# Left_Ear_Board.net
KiCad netlist of a schematic drawn in EAGLE
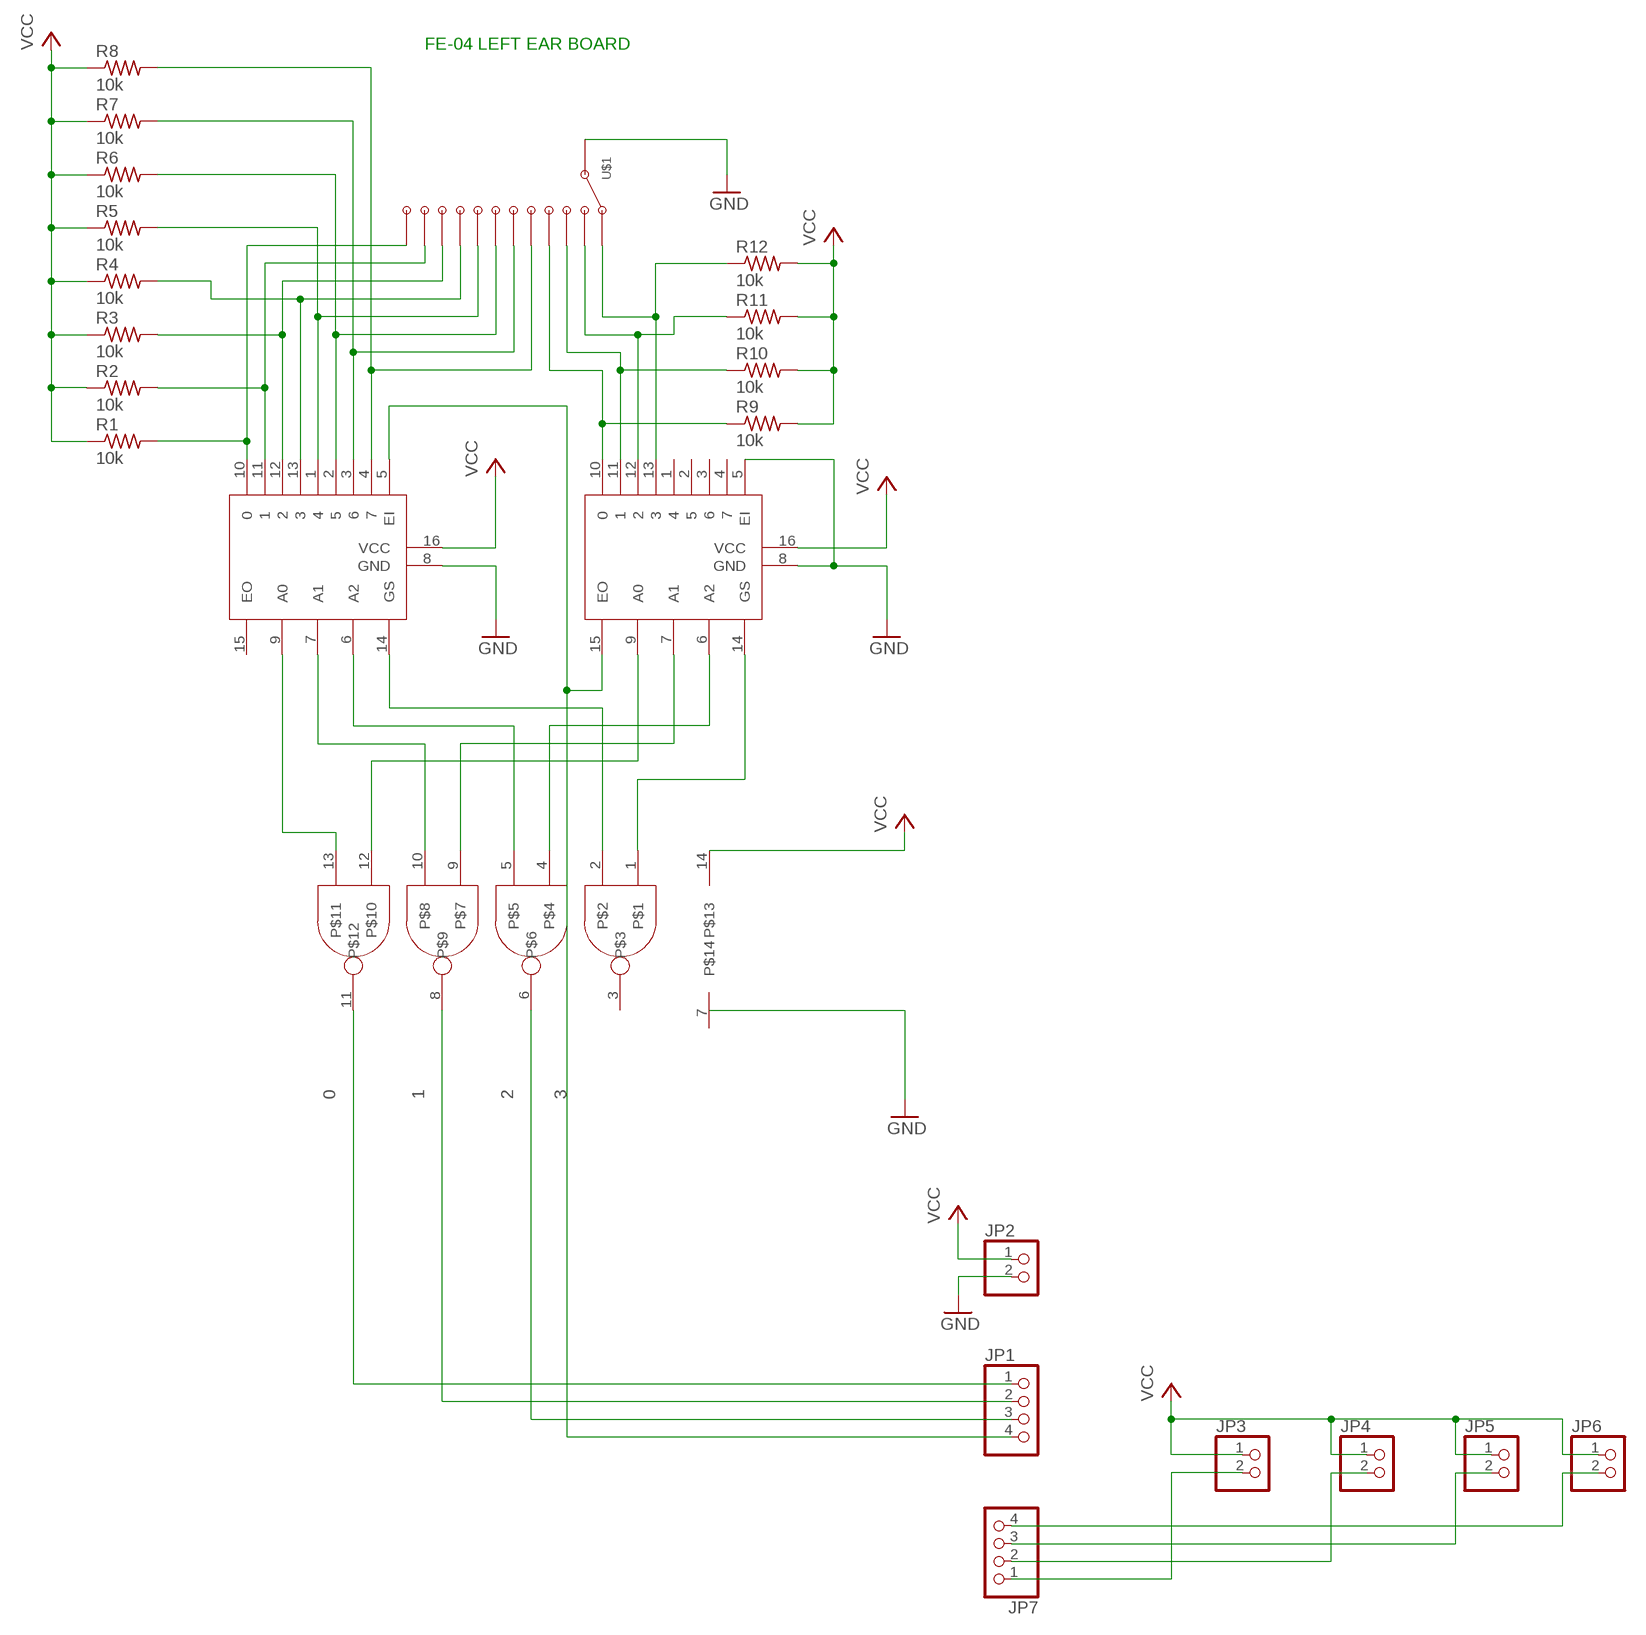
[diagram p0: schematic, sheet 1]

(export (version "E")
  (design (tool "Eeschema 10.0.6"))
  (components
    (comp (ref "JP1")
      (value "PINHD-1X4")
      (footprint "eagle-import:1X04")
      (libsource (lib "eagle-import") (part "PINHD-1X4"))
    )
    (comp (ref "JP2")
      (value "PINHD-1X2")
      (footprint "eagle-import:1X02")
      (libsource (lib "eagle-import") (part "PINHD-1X2"))
    )
    (comp (ref "JP3")
      (value "PINHD-1X2")
      (footprint "eagle-import:1X02")
      (libsource (lib "eagle-import") (part "PINHD-1X2"))
    )
    (comp (ref "JP4")
      (value "PINHD-1X2")
      (footprint "eagle-import:1X02")
      (libsource (lib "eagle-import") (part "PINHD-1X2"))
    )
    (comp (ref "JP5")
      (value "PINHD-1X2")
      (footprint "eagle-import:1X02")
      (libsource (lib "eagle-import") (part "PINHD-1X2"))
    )
    (comp (ref "JP6")
      (value "PINHD-1X2")
      (footprint "eagle-import:1X02")
      (libsource (lib "eagle-import") (part "PINHD-1X2"))
    )
    (comp (ref "JP7")
      (value "PINHD-1X4")
      (footprint "eagle-import:1X04")
      (libsource (lib "eagle-import") (part "PINHD-1X4"))
    )
    (comp (ref "R1")
      (value "10k")
      (footprint "eagle-import:R0603")
      (fields (field (name "PARTNO") "ERJ-3EKF2201V"))
      (libsource (lib "eagle-import") (part "R-US_R0603"))
    )
    (comp (ref "R2")
      (value "10k")
      (footprint "eagle-import:R0603")
      (fields (field (name "PARTNO") "ERJ-3EKF2201V"))
      (libsource (lib "eagle-import") (part "R-US_R0603"))
    )
    (comp (ref "R3")
      (value "10k")
      (footprint "eagle-import:R0603")
      (fields (field (name "PARTNO") "ERJ-3EKF2201V"))
      (libsource (lib "eagle-import") (part "R-US_R0603"))
    )
    (comp (ref "R4")
      (value "10k")
      (footprint "eagle-import:R0603")
      (fields (field (name "PARTNO") "ERJ-3EKF2201V"))
      (libsource (lib "eagle-import") (part "R-US_R0603"))
    )
    (comp (ref "R5")
      (value "10k")
      (footprint "eagle-import:R0603")
      (fields (field (name "PARTNO") "ERJ-3EKF2201V"))
      (libsource (lib "eagle-import") (part "R-US_R0603"))
    )
    (comp (ref "R6")
      (value "10k")
      (footprint "eagle-import:R0603")
      (fields (field (name "PARTNO") "ERJ-3EKF2201V"))
      (libsource (lib "eagle-import") (part "R-US_R0603"))
    )
    (comp (ref "R7")
      (value "10k")
      (footprint "eagle-import:R0603")
      (fields (field (name "PARTNO") "ERJ-3EKF2201V"))
      (libsource (lib "eagle-import") (part "R-US_R0603"))
    )
    (comp (ref "R8")
      (value "10k")
      (footprint "eagle-import:R0603")
      (fields (field (name "PARTNO") "ERJ-3EKF2201V"))
      (libsource (lib "eagle-import") (part "R-US_R0603"))
    )
    (comp (ref "R9")
      (value "10k")
      (footprint "eagle-import:R0603")
      (fields (field (name "PARTNO") "ERJ-3EKF2201V"))
      (libsource (lib "eagle-import") (part "R-US_R0603"))
    )
    (comp (ref "R10")
      (value "10k")
      (footprint "eagle-import:R0603")
      (fields (field (name "PARTNO") "ERJ-3EKF2201V"))
      (libsource (lib "eagle-import") (part "R-US_R0603"))
    )
    (comp (ref "R11")
      (value "10k")
      (footprint "eagle-import:R0603")
      (fields (field (name "PARTNO") "ERJ-3EKF2201V"))
      (libsource (lib "eagle-import") (part "R-US_R0603"))
    )
    (comp (ref "R12")
      (value "10k")
      (footprint "eagle-import:R0603")
      (fields (field (name "PARTNO") "ERJ-3EKF2201V"))
      (libsource (lib "eagle-import") (part "R-US_R0603"))
    )
    (comp (ref "U$1")
      (value "12-POSITION-ROTARY")
      (footprint "eagle-import:MC00L1NCQF")
      (libsource (lib "eagle-import") (part "12-POSITION-ROTARY"))
    )
    (comp (ref "U$2")
      (value "SN74LS148D")
      (footprint "eagle-import:SOIC-16")
      (libsource (lib "eagle-import") (part "SN74LS148D"))
    )
    (comp (ref "U$3")
      (value "SN74LS148D")
      (footprint "eagle-import:SOIC-16")
      (libsource (lib "eagle-import") (part "SN74LS148D"))
    )
    (comp (ref "U$4")
      (value "QUAD_NAND")
      (footprint "eagle-import:SOIC-14")
      (libsource (lib "eagle-import") (part "QUAD_NAND"))
    )
  )
  (nets
    (net (code "1") (name "/0") (class "Default")
      (node (ref "JP1") (pin "1") (pinfunction "1_1") (pintype "passive"))
      (node (ref "U$4") (pin "11") (pinfunction "P$12_11") (pintype "bidirectional"))
    )
    (net (code "2") (name "/1") (class "Default")
      (node (ref "JP1") (pin "2") (pinfunction "2_2") (pintype "passive"))
      (node (ref "U$4") (pin "8") (pinfunction "P$9_8") (pintype "bidirectional"))
    )
    (net (code "3") (name "/2") (class "Default")
      (node (ref "JP1") (pin "3") (pinfunction "3_3") (pintype "passive"))
      (node (ref "U$4") (pin "6") (pinfunction "P$6_6") (pintype "bidirectional"))
    )
    (net (code "4") (name "/3") (class "Default")
      (node (ref "JP1") (pin "4") (pinfunction "4_4") (pintype "passive"))
      (node (ref "U$2") (pin "5") (pinfunction "EI_5") (pintype "input"))
      (node (ref "U$3") (pin "15") (pinfunction "EO_15") (pintype "bidirectional"))
    )
    (net (code "5") (name "GND") (class "Default")
      (node (ref "JP2") (pin "2") (pinfunction "2_2") (pintype "passive"))
      (node (ref "U$1") (pin "P$13") (pinfunction "WIPER_P$13") (pintype "bidirectional"))
      (node (ref "U$2") (pin "8") (pinfunction "GND_8") (pintype "bidirectional"))
      (node (ref "U$3") (pin "5") (pinfunction "EI_5") (pintype "input"))
      (node (ref "U$3") (pin "8") (pinfunction "GND_8") (pintype "bidirectional"))
    )
    (net (code "6") (name "Net-(JP3-Pad2)") (class "Default")
      (node (ref "JP3") (pin "2") (pinfunction "2_2") (pintype "passive"))
      (node (ref "JP7") (pin "1") (pinfunction "1_1") (pintype "passive"))
    )
    (net (code "7") (name "Net-(JP4-Pad2)") (class "Default")
      (node (ref "JP4") (pin "2") (pinfunction "2_2") (pintype "passive"))
      (node (ref "JP7") (pin "2") (pinfunction "2_2") (pintype "passive"))
    )
    (net (code "8") (name "Net-(JP5-Pad2)") (class "Default")
      (node (ref "JP5") (pin "2") (pinfunction "2_2") (pintype "passive"))
      (node (ref "JP7") (pin "3") (pinfunction "3_3") (pintype "passive"))
    )
    (net (code "9") (name "Net-(JP6-Pad2)") (class "Default")
      (node (ref "JP6") (pin "2") (pinfunction "2_2") (pintype "passive"))
      (node (ref "JP7") (pin "4") (pinfunction "4_4") (pintype "passive"))
    )
    (net (code "10") (name "Net-(U$1-PIN1)") (class "Default")
      (node (ref "R12") (pin "1") (pinfunction "1_1") (pintype "passive"))
      (node (ref "U$1") (pin "P$1") (pinfunction "PIN1_P$1") (pintype "bidirectional"))
      (node (ref "U$3") (pin "13") (pinfunction "3_13") (pintype "input"))
    )
    (net (code "11") (name "Net-(U$1-PIN2)") (class "Default")
      (node (ref "R11") (pin "1") (pinfunction "1_1") (pintype "passive"))
      (node (ref "U$1") (pin "P$2") (pinfunction "PIN2_P$2") (pintype "bidirectional"))
      (node (ref "U$3") (pin "12") (pinfunction "2_12") (pintype "input"))
    )
    (net (code "12") (name "Net-(U$1-PIN3)") (class "Default")
      (node (ref "R10") (pin "1") (pinfunction "1_1") (pintype "passive"))
      (node (ref "U$1") (pin "P$3") (pinfunction "PIN3_P$3") (pintype "bidirectional"))
      (node (ref "U$3") (pin "11") (pinfunction "1_11") (pintype "input"))
    )
    (net (code "13") (name "Net-(U$1-PIN4)") (class "Default")
      (node (ref "R9") (pin "1") (pinfunction "1_1") (pintype "passive"))
      (node (ref "U$1") (pin "P$4") (pinfunction "PIN4_P$4") (pintype "bidirectional"))
      (node (ref "U$3") (pin "10") (pinfunction "0_10") (pintype "input"))
    )
    (net (code "14") (name "Net-(U$1-PIN5)") (class "Default")
      (node (ref "R8") (pin "2") (pinfunction "2_2") (pintype "passive"))
      (node (ref "U$1") (pin "P$5") (pinfunction "PIN5_P$5") (pintype "bidirectional"))
      (node (ref "U$2") (pin "4") (pinfunction "7_4") (pintype "input"))
    )
    (net (code "15") (name "Net-(U$1-PIN6)") (class "Default")
      (node (ref "R7") (pin "2") (pinfunction "2_2") (pintype "passive"))
      (node (ref "U$1") (pin "P$6") (pinfunction "PIN6_P$6") (pintype "bidirectional"))
      (node (ref "U$2") (pin "3") (pinfunction "6_3") (pintype "input"))
    )
    (net (code "16") (name "Net-(U$1-PIN7)") (class "Default")
      (node (ref "R6") (pin "2") (pinfunction "2_2") (pintype "passive"))
      (node (ref "U$1") (pin "P$7") (pinfunction "PIN7_P$7") (pintype "bidirectional"))
      (node (ref "U$2") (pin "2") (pinfunction "5_2") (pintype "input"))
    )
    (net (code "17") (name "Net-(U$1-PIN8)") (class "Default")
      (node (ref "R5") (pin "2") (pinfunction "2_2") (pintype "passive"))
      (node (ref "U$1") (pin "P$8") (pinfunction "PIN8_P$8") (pintype "bidirectional"))
      (node (ref "U$2") (pin "1") (pinfunction "4_1") (pintype "input"))
    )
    (net (code "18") (name "Net-(U$1-PIN9)") (class "Default")
      (node (ref "R4") (pin "2") (pinfunction "2_2") (pintype "passive"))
      (node (ref "U$1") (pin "P$9") (pinfunction "PIN9_P$9") (pintype "bidirectional"))
      (node (ref "U$2") (pin "13") (pinfunction "3_13") (pintype "input"))
    )
    (net (code "19") (name "Net-(U$1-PIN10)") (class "Default")
      (node (ref "R3") (pin "2") (pinfunction "2_2") (pintype "passive"))
      (node (ref "U$1") (pin "P$10") (pinfunction "PIN10_P$10") (pintype "bidirectional"))
      (node (ref "U$2") (pin "12") (pinfunction "2_12") (pintype "input"))
    )
    (net (code "20") (name "Net-(U$1-PIN11)") (class "Default")
      (node (ref "R2") (pin "2") (pinfunction "2_2") (pintype "passive"))
      (node (ref "U$1") (pin "P$11") (pinfunction "PIN11_P$11") (pintype "bidirectional"))
      (node (ref "U$2") (pin "11") (pinfunction "1_11") (pintype "input"))
    )
    (net (code "21") (name "Net-(U$1-PIN12)") (class "Default")
      (node (ref "R1") (pin "2") (pinfunction "2_2") (pintype "passive"))
      (node (ref "U$1") (pin "P$12") (pinfunction "PIN12_P$12") (pintype "bidirectional"))
      (node (ref "U$2") (pin "10") (pinfunction "0_10") (pintype "input"))
    )
    (net (code "22") (name "Net-(U$2-A0)") (class "Default")
      (node (ref "U$2") (pin "9") (pinfunction "A0_9") (pintype "bidirectional"))
      (node (ref "U$4") (pin "13") (pinfunction "P$11_13") (pintype "bidirectional"))
    )
    (net (code "23") (name "Net-(U$2-A1)") (class "Default")
      (node (ref "U$2") (pin "7") (pinfunction "A1_7") (pintype "bidirectional"))
      (node (ref "U$4") (pin "10") (pinfunction "P$8_10") (pintype "bidirectional"))
    )
    (net (code "24") (name "Net-(U$2-A2)") (class "Default")
      (node (ref "U$2") (pin "6") (pinfunction "A2_6") (pintype "bidirectional"))
      (node (ref "U$4") (pin "5") (pinfunction "P$5_5") (pintype "bidirectional"))
    )
    (net (code "25") (name "Net-(U$2-GS)") (class "Default")
      (node (ref "U$2") (pin "14") (pinfunction "GS_14") (pintype "bidirectional"))
      (node (ref "U$4") (pin "2") (pinfunction "P$2_2") (pintype "bidirectional"))
    )
    (net (code "26") (name "Net-(U$3-A0)") (class "Default")
      (node (ref "U$3") (pin "9") (pinfunction "A0_9") (pintype "bidirectional"))
      (node (ref "U$4") (pin "12") (pinfunction "P$10_12") (pintype "bidirectional"))
    )
    (net (code "27") (name "Net-(U$3-A1)") (class "Default")
      (node (ref "U$3") (pin "7") (pinfunction "A1_7") (pintype "bidirectional"))
      (node (ref "U$4") (pin "9") (pinfunction "P$7_9") (pintype "bidirectional"))
    )
    (net (code "28") (name "Net-(U$3-A2)") (class "Default")
      (node (ref "U$3") (pin "6") (pinfunction "A2_6") (pintype "bidirectional"))
      (node (ref "U$4") (pin "4") (pinfunction "P$4_4") (pintype "bidirectional"))
    )
    (net (code "29") (name "Net-(U$3-GS)") (class "Default")
      (node (ref "U$3") (pin "14") (pinfunction "GS_14") (pintype "bidirectional"))
      (node (ref "U$4") (pin "1") (pinfunction "P$1_1") (pintype "bidirectional"))
    )
    (net (code "30") (name "VCC") (class "Default")
      (node (ref "JP2") (pin "1") (pinfunction "1_1") (pintype "passive"))
      (node (ref "JP3") (pin "1") (pinfunction "1_1") (pintype "passive"))
      (node (ref "JP4") (pin "1") (pinfunction "1_1") (pintype "passive"))
      (node (ref "JP5") (pin "1") (pinfunction "1_1") (pintype "passive"))
      (node (ref "JP6") (pin "1") (pinfunction "1_1") (pintype "passive"))
      (node (ref "R1") (pin "1") (pinfunction "1_1") (pintype "passive"))
      (node (ref "R10") (pin "2") (pinfunction "2_2") (pintype "passive"))
      (node (ref "R11") (pin "2") (pinfunction "2_2") (pintype "passive"))
      (node (ref "R12") (pin "2") (pinfunction "2_2") (pintype "passive"))
      (node (ref "R2") (pin "1") (pinfunction "1_1") (pintype "passive"))
      (node (ref "R3") (pin "1") (pinfunction "1_1") (pintype "passive"))
      (node (ref "R4") (pin "1") (pinfunction "1_1") (pintype "passive"))
      (node (ref "R5") (pin "1") (pinfunction "1_1") (pintype "passive"))
      (node (ref "R6") (pin "1") (pinfunction "1_1") (pintype "passive"))
      (node (ref "R7") (pin "1") (pinfunction "1_1") (pintype "passive"))
      (node (ref "R8") (pin "1") (pinfunction "1_1") (pintype "passive"))
      (node (ref "R9") (pin "2") (pinfunction "2_2") (pintype "passive"))
      (node (ref "U$2") (pin "16") (pinfunction "VCC_16") (pintype "bidirectional"))
      (node (ref "U$3") (pin "16") (pinfunction "VCC_16") (pintype "bidirectional"))
      (node (ref "U$4") (pin "14") (pinfunction "P$13_14") (pintype "bidirectional"))
    )
    (net (code "31") (name "unconnected-(U$2-EO-Pad15)") (class "Default")
      (node (ref "U$2") (pin "15") (pinfunction "EO_15") (pintype "bidirectional"))
    )
    (net (code "32") (name "unconnected-(U$3-4-Pad1)") (class "Default")
      (node (ref "U$3") (pin "1") (pinfunction "4_1") (pintype "input"))
    )
    (net (code "33") (name "unconnected-(U$3-5-Pad2)") (class "Default")
      (node (ref "U$3") (pin "2") (pinfunction "5_2") (pintype "input"))
    )
    (net (code "34") (name "unconnected-(U$3-6-Pad3)") (class "Default")
      (node (ref "U$3") (pin "3") (pinfunction "6_3") (pintype "input"))
    )
    (net (code "35") (name "unconnected-(U$3-7-Pad4)") (class "Default")
      (node (ref "U$3") (pin "4") (pinfunction "7_4") (pintype "input"))
    )
    (net (code "36") (name "unconnected-(U$4-P$3-Pad3)") (class "Default")
      (node (ref "U$4") (pin "3") (pinfunction "P$3_3") (pintype "bidirectional"))
    )
    (net (code "37") (name "unconnected-(U$4-P$14-Pad7)") (class "Default")
      (node (ref "U$4") (pin "7") (pinfunction "P$14_7") (pintype "bidirectional"))
    )
  )
)
